# VGA.net
KiCad netlist of a schematic drawn in Altium Designer
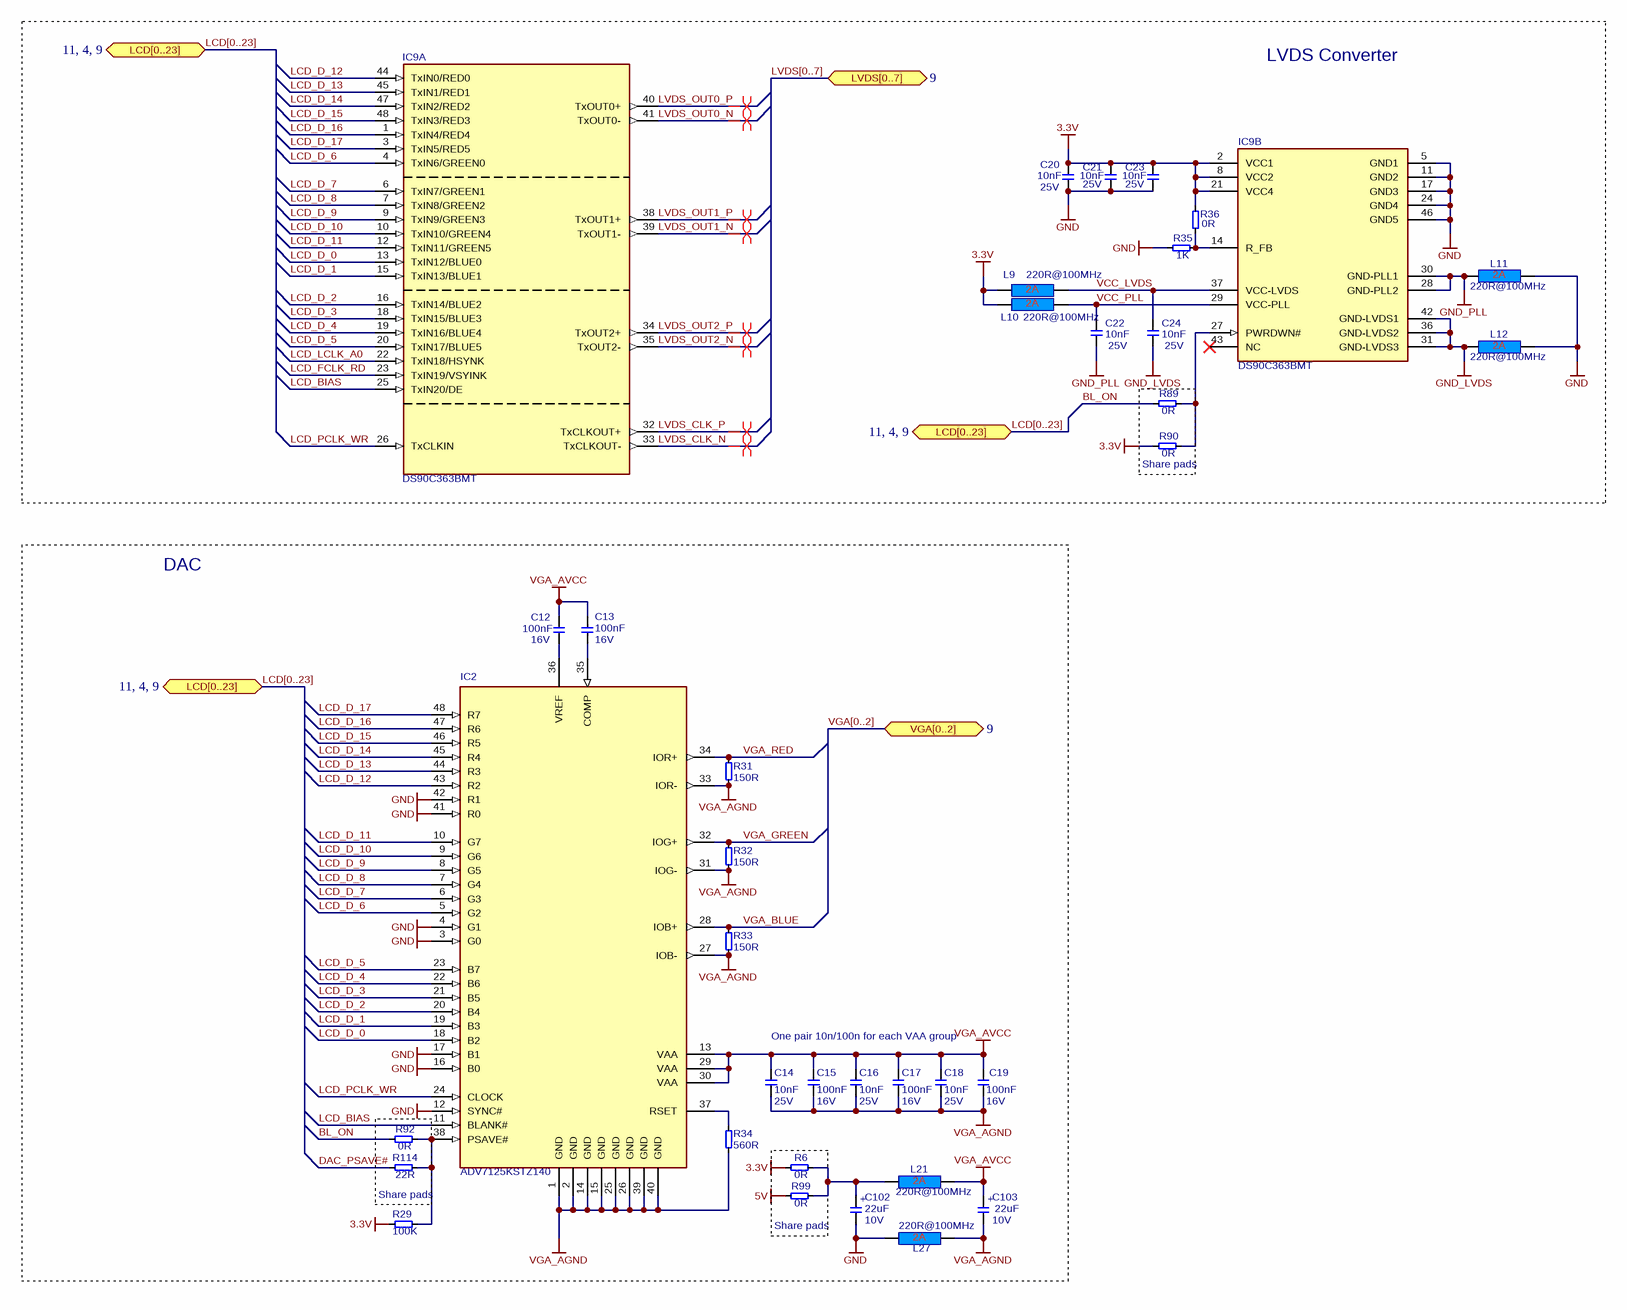
[diagram p0: VGA.SchDoc]

(export (version "E")
  (design (tool "Eeschema 10.0.6"))
  (components
    (comp (ref "C12")
      (value "100nF")
      (footprint "T_CAPC0603X33N")
      (description "Capacitor Ceramic X7R 100nF 16V 10% 0603")
      (fields (field (name "TOLERANCE") "10%") (field (name "RATING") "16V"))
      (libsource (lib "Iris") (part "C-X7R-100nF-16V-10%-0603"))
    )
    (comp (ref "C13")
      (value "100nF")
      (footprint "T_CAPC0603X33N")
      (description "Capacitor Ceramic X7R 100nF 16V 10% 0603")
      (fields (field (name "TOLERANCE") "10%") (field (name "RATING") "16V"))
      (libsource (lib "Iris") (part "C-X7R-100nF-16V-10%-0603"))
    )
    (comp (ref "C14")
      (value "10nF")
      (footprint "T_CAPC0603X33N")
      (description "Capacitor Ceramic X7R 10nF 25V 10% 0603")
      (fields (field (name "TOLERANCE") "10%") (field (name "RATING") "25V"))
      (libsource (lib "Iris") (part "C-X7R-10nF-25V-10%-0603"))
    )
    (comp (ref "C15")
      (value "100nF")
      (footprint "T_CAPC0603X33N")
      (description "Capacitor Ceramic X7R 100nF 16V 10% 0603")
      (fields (field (name "TOLERANCE") "10%") (field (name "RATING") "16V"))
      (libsource (lib "Iris") (part "C-X7R-100nF-16V-10%-0603"))
    )
    (comp (ref "C16")
      (value "10nF")
      (footprint "T_CAPC0603X33N")
      (description "Capacitor Ceramic X7R 10nF 25V 10% 0603")
      (fields (field (name "TOLERANCE") "10%") (field (name "RATING") "25V"))
      (libsource (lib "Iris") (part "C-X7R-10nF-25V-10%-0603"))
    )
    (comp (ref "C17")
      (value "100nF")
      (footprint "T_CAPC0603X33N")
      (description "Capacitor Ceramic X7R 100nF 16V 10% 0603")
      (fields (field (name "TOLERANCE") "10%") (field (name "RATING") "16V"))
      (libsource (lib "Iris") (part "C-X7R-100nF-16V-10%-0603"))
    )
    (comp (ref "C18")
      (value "10nF")
      (footprint "T_CAPC0603X33N")
      (description "Capacitor Ceramic X7R 10nF 25V 10% 0603")
      (fields (field (name "TOLERANCE") "10%") (field (name "RATING") "25V"))
      (libsource (lib "Iris") (part "C-X7R-10nF-25V-10%-0603"))
    )
    (comp (ref "C19")
      (value "100nF")
      (footprint "T_CAPC0603X33N")
      (description "Capacitor Ceramic X7R 100nF 16V 10% 0603")
      (fields (field (name "TOLERANCE") "10%") (field (name "RATING") "16V"))
      (libsource (lib "Iris") (part "C-X7R-100nF-16V-10%-0603"))
    )
    (comp (ref "C20")
      (value "10nF")
      (footprint "T_CAPC0603X33N")
      (description "Capacitor Ceramic X7R 10nF 25V 10% 0603")
      (fields (field (name "TOLERANCE") "10%") (field (name "RATING") "25V"))
      (libsource (lib "Iris") (part "C-X7R-10nF-25V-10%-0603"))
    )
    (comp (ref "C21")
      (value "10nF")
      (footprint "T_CAPC0603X33N")
      (description "Capacitor Ceramic X7R 10nF 25V 10% 0603")
      (fields (field (name "TOLERANCE") "10%") (field (name "RATING") "25V"))
      (libsource (lib "Iris") (part "C-X7R-10nF-25V-10%-0603"))
    )
    (comp (ref "C22")
      (value "10nF")
      (footprint "T_CAPC0603X33N")
      (description "Capacitor Ceramic X7R 10nF 25V 10% 0603")
      (fields (field (name "TOLERANCE") "10%") (field (name "RATING") "25V"))
      (libsource (lib "Iris") (part "C-X7R-10nF-25V-10%-0603"))
    )
    (comp (ref "C23")
      (value "10nF")
      (footprint "T_CAPC0603X33N")
      (description "Capacitor Ceramic X7R 10nF 25V 10% 0603")
      (fields (field (name "TOLERANCE") "10%") (field (name "RATING") "25V"))
      (libsource (lib "Iris") (part "C-X7R-10nF-25V-10%-0603"))
    )
    (comp (ref "C24")
      (value "10nF")
      (footprint "T_CAPC0603X33N")
      (description "Capacitor Ceramic X7R 10nF 25V 10% 0603")
      (fields (field (name "TOLERANCE") "10%") (field (name "RATING") "25V"))
      (libsource (lib "Iris") (part "C-X7R-10nF-25V-10%-0603"))
    )
    (comp (ref "C102")
      (value "22uF")
      (footprint "CAPMP3528X210N")
      (description "Capacitor TA 22uF 10V 20% 3528")
      (fields (field (name "TOLERANCE") "20%") (field (name "RATING") "10V"))
      (libsource (lib "Iris") (part "C-TA-22uF-10V-20%-3528"))
    )
    (comp (ref "C103")
      (value "22uF")
      (footprint "CAPMP3528X210N")
      (description "Capacitor TA 22uF 10V 20% 3528")
      (fields (field (name "TOLERANCE") "20%") (field (name "RATING") "10V"))
      (libsource (lib "Iris") (part "C-TA-22uF-10V-20%-3528"))
    )
    (comp (ref "IC2")
      (value "ADV7125KSTZ140")
      (footprint "QFP50P900X900X120-48N")
      (description "Video DAC 8bit 140MHz")
      (fields (field (name "MANUFACTURER PART NO.") "ADV7125KSTZ140"))
      (libsource (lib "Iris") (part "IC-AD-ADV7125KSTZ140"))
    )
    (comp (ref "IC9")
      (value "DS90C363BMT")
      (footprint "SOP50P810X120-48N")
      (description "LVDS Converter")
      (fields (field (name "MANUFACTURER PART NO.") "DS90C363BMT"))
      (libsource (lib "Iris") (part "IC-NS-DS90C363BMT"))
    )
    (comp (ref "L9")
      (value "220R@100MHz")
      (footprint "INDC1608X95N")
      (description "220R@100MHz 2A EMI FILTER")
      (fields (field (name "TOLERANCE") "25%"))
      (libsource (lib "Iris") (part "L-220R@100MHz-2A-25%-0603"))
    )
    (comp (ref "L10")
      (value "220R@100MHz")
      (footprint "INDC1608X95N")
      (description "220R@100MHz 2A EMI FILTER")
      (fields (field (name "TOLERANCE") "25%"))
      (libsource (lib "Iris") (part "L-220R@100MHz-2A-25%-0603"))
    )
    (comp (ref "L11")
      (value "220R@100MHz")
      (footprint "INDC1608X95N")
      (description "220R@100MHz 2A EMI FILTER")
      (fields (field (name "TOLERANCE") "25%"))
      (libsource (lib "Iris") (part "L-220R@100MHz-2A-25%-0603"))
    )
    (comp (ref "L12")
      (value "220R@100MHz")
      (footprint "INDC1608X95N")
      (description "220R@100MHz 2A EMI FILTER")
      (fields (field (name "TOLERANCE") "25%"))
      (libsource (lib "Iris") (part "L-220R@100MHz-2A-25%-0603"))
    )
    (comp (ref "L21")
      (value "220R@100MHz")
      (footprint "INDC1608X95N")
      (description "220R@100MHz 2A EMI FILTER")
      (fields (field (name "TOLERANCE") "25%"))
      (libsource (lib "Iris") (part "L-220R@100MHz-2A-25%-0603"))
    )
    (comp (ref "L27")
      (value "220R@100MHz")
      (footprint "INDC1608X95N")
      (description "220R@100MHz 2A EMI FILTER")
      (fields (field (name "TOLERANCE") "25%"))
      (libsource (lib "Iris") (part "L-220R@100MHz-2A-25%-0603"))
    )
    (comp (ref "R6")
      (value "0R")
      (footprint "T_RESC0603X30N")
      (description "Resistor 0 ohm 63mW 1% 0603")
      (fields (field (name "TOLERANCE") "1%"))
      (libsource (lib "Iris") (part "R-0R-63mW-1%-0603"))
    )
    (comp (ref "R29")
      (value "100K")
      (footprint "T_RESC0603X30N")
      (description "Resistor 100 Kohm 63mW 5% 0603")
      (fields (field (name "TOLERANCE") "5%"))
      (libsource (lib "Iris") (part "R-100KR-63mW-5%-0603"))
    )
    (comp (ref "R31")
      (value "150R")
      (footprint "T_RESC0603X30N")
      (description "Resistor 150 ohm 63mW 1% 0603")
      (fields (field (name "TOLERANCE") "1%"))
      (libsource (lib "Iris") (part "R-150R-63mW-1%-0603"))
    )
    (comp (ref "R32")
      (value "150R")
      (footprint "T_RESC0603X30N")
      (description "Resistor 150 ohm 63mW 1% 0603")
      (fields (field (name "TOLERANCE") "1%"))
      (libsource (lib "Iris") (part "R-150R-63mW-1%-0603"))
    )
    (comp (ref "R33")
      (value "150R")
      (footprint "T_RESC0603X30N")
      (description "Resistor 150 ohm 63mW 1% 0603")
      (fields (field (name "TOLERANCE") "1%"))
      (libsource (lib "Iris") (part "R-150R-63mW-1%-0603"))
    )
    (comp (ref "R34")
      (value "560R")
      (footprint "t_RESC0603X30N")
      (description "Resistor 560 ohm 63mW 5% 0603")
      (fields (field (name "TOLERANCE") "5%"))
      (libsource (lib "Iris") (part "R-560R-63mW-5%-0603"))
    )
    (comp (ref "R35")
      (value "1K")
      (footprint "t_RESC0603X30N")
      (description "Resistor 1 Kohm 63mW 5% 0603")
      (fields (field (name "TOLERANCE") "5%"))
      (libsource (lib "Iris") (part "R-1KR-63mW-5%-0603"))
    )
    (comp (ref "R36")
      (value "0R")
      (footprint "t_RESC0603X30N")
      (description "Resistor 0 ohm 63mW 1% 0603")
      (fields (field (name "TOLERANCE") "1%"))
      (libsource (lib "Iris") (part "R-0R-63mW-1%-0603"))
    )
    (comp (ref "R89")
      (value "0R")
      (footprint "t_RESC0603X30N")
      (description "Resistor 0 ohm 63mW 1% 0603")
      (fields (field (name "TOLERANCE") "1%"))
      (libsource (lib "Iris") (part "R-0R-63mW-1%-0603"))
    )
    (comp (ref "R90")
      (value "0R")
      (footprint "t_RESC0603X30N")
      (description "Resistor 0 ohm 63mW 1% 0603")
      (fields (field (name "TOLERANCE") "1%"))
      (libsource (lib "Iris") (part "R-0R-63mW-1%-0603"))
    )
    (comp (ref "R92")
      (value "0R")
      (footprint "T_RESC0603X30N")
      (description "Resistor 0 ohm 63mW 1% 0603")
      (fields (field (name "TOLERANCE") "1%"))
      (libsource (lib "Iris") (part "R-0R-63mW-1%-0603"))
    )
    (comp (ref "R99")
      (value "0R")
      (footprint "T_RESC0603X30N")
      (description "Resistor 0 ohm 63mW 1% 0603")
      (fields (field (name "TOLERANCE") "1%"))
      (libsource (lib "Iris") (part "R-0R-63mW-1%-0603"))
    )
    (comp (ref "R114")
      (value "22R")
      (footprint "T_RESC0603X30N")
      (description "Resistor 22 ohm 63mW 5% 0603")
      (fields (field (name "TOLERANCE") "5%"))
      (libsource (lib "Iris") (part "R-22R-63mW-5%-0603"))
    )
  )
  (nets
    (net (code "36") (name "/BL_ON") (class "Default")
      (node (ref "R89") (pin "1") (pinfunction "1_1") (pintype "passive"))
      (node (ref "R92") (pin "1") (pinfunction "1_1") (pintype "passive"))
    )
    (net (code "37") (name "/DAC_PSAVE#") (class "Default")
      (node (ref "R114") (pin "1") (pinfunction "1_1") (pintype "passive"))
    )
    (net (code "39") (name "/LCD_BIAS") (class "Default")
      (node (ref "IC2") (pin "11") (pinfunction "BLANK#_11") (pintype "input"))
      (node (ref "IC9") (pin "25") (pinfunction "TxIN20/DE_25") (pintype "input"))
    )
    (net (code "40") (name "/LCD_D_0") (class "Default")
      (node (ref "IC2") (pin "18") (pinfunction "B2_18") (pintype "input"))
      (node (ref "IC9") (pin "13") (pinfunction "TxIN12/BLUE0_13") (pintype "input"))
    )
    (net (code "41") (name "/LCD_D_1") (class "Default")
      (node (ref "IC2") (pin "19") (pinfunction "B3_19") (pintype "input"))
      (node (ref "IC9") (pin "15") (pinfunction "TxIN13/BLUE1_15") (pintype "input"))
    )
    (net (code "42") (name "/LCD_D_2") (class "Default")
      (node (ref "IC2") (pin "20") (pinfunction "B4_20") (pintype "input"))
      (node (ref "IC9") (pin "16") (pinfunction "TxIN14/BLUE2_16") (pintype "input"))
    )
    (net (code "43") (name "/LCD_D_3") (class "Default")
      (node (ref "IC2") (pin "21") (pinfunction "B5_21") (pintype "input"))
      (node (ref "IC9") (pin "18") (pinfunction "TxIN15/BLUE3_18") (pintype "input"))
    )
    (net (code "44") (name "/LCD_D_4") (class "Default")
      (node (ref "IC2") (pin "22") (pinfunction "B6_22") (pintype "input"))
      (node (ref "IC9") (pin "19") (pinfunction "TxIN16/BLUE4_19") (pintype "input"))
    )
    (net (code "45") (name "/LCD_D_5") (class "Default")
      (node (ref "IC2") (pin "23") (pinfunction "B7_23") (pintype "input"))
      (node (ref "IC9") (pin "20") (pinfunction "TxIN17/BLUE5_20") (pintype "input"))
    )
    (net (code "46") (name "/LCD_D_6") (class "Default")
      (node (ref "IC2") (pin "5") (pinfunction "G2_5") (pintype "input"))
      (node (ref "IC9") (pin "4") (pinfunction "TxIN6/GREEN0_4") (pintype "input"))
    )
    (net (code "47") (name "/LCD_D_7") (class "Default")
      (node (ref "IC2") (pin "6") (pinfunction "G3_6") (pintype "input"))
      (node (ref "IC9") (pin "6") (pinfunction "TxIN7/GREEN1_6") (pintype "input"))
    )
    (net (code "48") (name "/LCD_D_8") (class "Default")
      (node (ref "IC2") (pin "7") (pinfunction "G4_7") (pintype "input"))
      (node (ref "IC9") (pin "7") (pinfunction "TxIN8/GREEN2_7") (pintype "input"))
    )
    (net (code "49") (name "/LCD_D_9") (class "Default")
      (node (ref "IC2") (pin "8") (pinfunction "G5_8") (pintype "input"))
      (node (ref "IC9") (pin "9") (pinfunction "TxIN9/GREEN3_9") (pintype "input"))
    )
    (net (code "50") (name "/LCD_D_10") (class "Default")
      (node (ref "IC2") (pin "9") (pinfunction "G6_9") (pintype "input"))
      (node (ref "IC9") (pin "10") (pinfunction "TxIN10/GREEN4_10") (pintype "input"))
    )
    (net (code "51") (name "/LCD_D_11") (class "Default")
      (node (ref "IC2") (pin "10") (pinfunction "G7_10") (pintype "input"))
      (node (ref "IC9") (pin "12") (pinfunction "TxIN11/GREEN5_12") (pintype "input"))
    )
    (net (code "52") (name "/LCD_D_12") (class "Default")
      (node (ref "IC2") (pin "43") (pinfunction "R2_43") (pintype "input"))
      (node (ref "IC9") (pin "44") (pinfunction "TxIN0/RED0_44") (pintype "input"))
    )
    (net (code "53") (name "/LCD_D_13") (class "Default")
      (node (ref "IC2") (pin "44") (pinfunction "R3_44") (pintype "input"))
      (node (ref "IC9") (pin "45") (pinfunction "TxIN1/RED1_45") (pintype "input"))
    )
    (net (code "54") (name "/LCD_D_14") (class "Default")
      (node (ref "IC2") (pin "45") (pinfunction "R4_45") (pintype "input"))
      (node (ref "IC9") (pin "47") (pinfunction "TxIN2/RED2_47") (pintype "input"))
    )
    (net (code "55") (name "/LCD_D_15") (class "Default")
      (node (ref "IC2") (pin "46") (pinfunction "R5_46") (pintype "input"))
      (node (ref "IC9") (pin "48") (pinfunction "TxIN3/RED3_48") (pintype "input"))
    )
    (net (code "56") (name "/LCD_D_16") (class "Default")
      (node (ref "IC2") (pin "47") (pinfunction "R6_47") (pintype "input"))
      (node (ref "IC9") (pin "1") (pinfunction "TxIN4/RED4_1") (pintype "input"))
    )
    (net (code "57") (name "/LCD_D_17") (class "Default")
      (node (ref "IC2") (pin "48") (pinfunction "R7_48") (pintype "input"))
      (node (ref "IC9") (pin "3") (pinfunction "TxIN5/RED5_3") (pintype "input"))
    )
    (net (code "58") (name "/LCD_FCLK_RD") (class "Default")
      (node (ref "IC9") (pin "23") (pinfunction "TxIN19/VSYINK_23") (pintype "input"))
    )
    (net (code "59") (name "/LCD_LCLK_A0") (class "Default")
      (node (ref "IC9") (pin "22") (pinfunction "TxIN18/HSYNK_22") (pintype "input"))
    )
    (net (code "60") (name "/LCD_PCLK_WR") (class "Default")
      (node (ref "IC2") (pin "24") (pinfunction "CLOCK_24") (pintype "input"))
      (node (ref "IC9") (pin "26") (pinfunction "TxCLKIN_26") (pintype "input"))
    )
    (net (code "62") (name "/LVDS_CLK_N") (class "Default")
      (node (ref "IC9") (pin "33") (pinfunction "TxCLKOUT-_33") (pintype "output"))
    )
    (net (code "63") (name "/LVDS_CLK_P") (class "Default")
      (node (ref "IC9") (pin "32") (pinfunction "TxCLKOUT+_32") (pintype "output"))
    )
    (net (code "64") (name "/LVDS_OUT0_N") (class "Default")
      (node (ref "IC9") (pin "41") (pinfunction "TxOUT0-_41") (pintype "output"))
    )
    (net (code "65") (name "/LVDS_OUT0_P") (class "Default")
      (node (ref "IC9") (pin "40") (pinfunction "TxOUT0+_40") (pintype "output"))
    )
    (net (code "66") (name "/LVDS_OUT1_N") (class "Default")
      (node (ref "IC9") (pin "39") (pinfunction "TxOUT1-_39") (pintype "output"))
    )
    (net (code "67") (name "/LVDS_OUT1_P") (class "Default")
      (node (ref "IC9") (pin "38") (pinfunction "TxOUT1+_38") (pintype "output"))
    )
    (net (code "68") (name "/LVDS_OUT2_N") (class "Default")
      (node (ref "IC9") (pin "35") (pinfunction "TxOUT2-_35") (pintype "output"))
    )
    (net (code "69") (name "/LVDS_OUT2_P") (class "Default")
      (node (ref "IC9") (pin "34") (pinfunction "TxOUT2+_34") (pintype "output"))
    )
    (net (code "70") (name "/VCC_LVDS") (class "Default")
      (node (ref "C24") (pin "2") (pinfunction "2_2") (pintype "passive"))
      (node (ref "IC9") (pin "37") (pinfunction "VCC-LVDS_37") (pintype "power_in"))
      (node (ref "L9") (pin "2") (pinfunction "2_2") (pintype "passive"))
    )
    (net (code "71") (name "/VCC_PLL") (class "Default")
      (node (ref "C22") (pin "2") (pinfunction "2_2") (pintype "passive"))
      (node (ref "IC9") (pin "29") (pinfunction "VCC-PLL_29") (pintype "power_in"))
      (node (ref "L10") (pin "2") (pinfunction "2_2") (pintype "passive"))
    )
    (net (code "73") (name "/VGA_BLUE") (class "Default")
      (node (ref "IC2") (pin "28") (pinfunction "IOB+_28") (pintype "output"))
      (node (ref "R33") (pin "2") (pinfunction "2_2") (pintype "passive"))
    )
    (net (code "74") (name "/VGA_GREEN") (class "Default")
      (node (ref "IC2") (pin "32") (pinfunction "IOG+_32") (pintype "output"))
      (node (ref "R32") (pin "2") (pinfunction "2_2") (pintype "passive"))
    )
    (net (code "75") (name "/VGA_RED") (class "Default")
      (node (ref "IC2") (pin "34") (pinfunction "IOR+_34") (pintype "output"))
      (node (ref "R31") (pin "2") (pinfunction "2_2") (pintype "passive"))
    )
    (net (code "76") (name "3.3V") (class "Default")
      (node (ref "C20") (pin "2") (pinfunction "2_2") (pintype "passive"))
      (node (ref "C21") (pin "2") (pinfunction "2_2") (pintype "passive"))
      (node (ref "C23") (pin "2") (pinfunction "2_2") (pintype "passive"))
      (node (ref "IC9") (pin "2") (pinfunction "VCC1_2") (pintype "power_in"))
      (node (ref "IC9") (pin "21") (pinfunction "VCC4_21") (pintype "power_in"))
      (node (ref "IC9") (pin "8") (pinfunction "VCC2_8") (pintype "power_in"))
      (node (ref "L10") (pin "1") (pinfunction "1_1") (pintype "passive"))
      (node (ref "L9") (pin "1") (pinfunction "1_1") (pintype "passive"))
      (node (ref "R29") (pin "1") (pinfunction "1_1") (pintype "passive"))
      (node (ref "R36") (pin "2") (pinfunction "2_2") (pintype "passive"))
      (node (ref "R6") (pin "1") (pinfunction "1_1") (pintype "passive"))
      (node (ref "R90") (pin "1") (pinfunction "1_1") (pintype "passive"))
    )
    (net (code "77") (name "5V") (class "Default")
      (node (ref "R99") (pin "1") (pinfunction "1_1") (pintype "passive"))
    )
    (net (code "78") (name "GND") (class "Default")
      (node (ref "C102") (pin "2") (pinfunction "2_2") (pintype "passive"))
      (node (ref "C20") (pin "1") (pinfunction "1_1") (pintype "passive"))
      (node (ref "C21") (pin "1") (pinfunction "1_1") (pintype "passive"))
      (node (ref "C23") (pin "1") (pinfunction "1_1") (pintype "passive"))
      (node (ref "IC2") (pin "12") (pinfunction "SYNC#_12") (pintype "input"))
      (node (ref "IC2") (pin "16") (pinfunction "B0_16") (pintype "input"))
      (node (ref "IC2") (pin "17") (pinfunction "B1_17") (pintype "input"))
      (node (ref "IC2") (pin "3") (pinfunction "G0_3") (pintype "input"))
      (node (ref "IC2") (pin "4") (pinfunction "G1_4") (pintype "input"))
      (node (ref "IC2") (pin "41") (pinfunction "R0_41") (pintype "input"))
      (node (ref "IC2") (pin "42") (pinfunction "R1_42") (pintype "input"))
      (node (ref "IC9") (pin "11") (pinfunction "GND2_11") (pintype "power_in"))
      (node (ref "IC9") (pin "17") (pinfunction "GND3_17") (pintype "power_in"))
      (node (ref "IC9") (pin "24") (pinfunction "GND4_24") (pintype "power_in"))
      (node (ref "IC9") (pin "46") (pinfunction "GND5_46") (pintype "power_in"))
      (node (ref "IC9") (pin "5") (pinfunction "GND1_5") (pintype "power_in"))
      (node (ref "L11") (pin "2") (pinfunction "2_2") (pintype "passive"))
      (node (ref "L12") (pin "2") (pinfunction "2_2") (pintype "passive"))
      (node (ref "L27") (pin "1") (pinfunction "1_1") (pintype "passive"))
      (node (ref "R35") (pin "1") (pinfunction "1_1") (pintype "passive"))
    )
    (net (code "79") (name "GND_LVDS") (class "Default")
      (node (ref "C24") (pin "1") (pinfunction "1_1") (pintype "passive"))
      (node (ref "IC9") (pin "31") (pinfunction "GND-LVDS3_31") (pintype "power_in"))
      (node (ref "IC9") (pin "36") (pinfunction "GND-LVDS2_36") (pintype "power_in"))
      (node (ref "IC9") (pin "42") (pinfunction "GND-LVDS1_42") (pintype "power_in"))
      (node (ref "L12") (pin "1") (pinfunction "1_1") (pintype "passive"))
    )
    (net (code "80") (name "GND_PLL") (class "Default")
      (node (ref "C22") (pin "1") (pinfunction "1_1") (pintype "passive"))
      (node (ref "IC9") (pin "28") (pinfunction "GND-PLL2_28") (pintype "power_in"))
      (node (ref "IC9") (pin "30") (pinfunction "GND-PLL1_30") (pintype "power_in"))
      (node (ref "L11") (pin "1") (pinfunction "1_1") (pintype "passive"))
    )
    (net (code "81") (name "Net-(C102-Pad1)") (class "Default")
      (node (ref "C102") (pin "1") (pinfunction "1_1") (pintype "passive"))
      (node (ref "L21") (pin "1") (pinfunction "1_1") (pintype "passive"))
      (node (ref "R6") (pin "2") (pinfunction "2_2") (pintype "passive"))
      (node (ref "R99") (pin "2") (pinfunction "2_2") (pintype "passive"))
    )
    (net (code "82") (name "Net-(IC2-COMP)") (class "Default")
      (node (ref "C13") (pin "1") (pinfunction "1_1") (pintype "passive"))
      (node (ref "IC2") (pin "35") (pinfunction "COMP_35") (pintype "input"))
    )
    (net (code "83") (name "Net-(IC2-PSAVE#)") (class "Default")
      (node (ref "IC2") (pin "38") (pinfunction "PSAVE#_38") (pintype "input"))
      (node (ref "R114") (pin "2") (pinfunction "2_2") (pintype "passive"))
      (node (ref "R29") (pin "2") (pinfunction "2_2") (pintype "passive"))
      (node (ref "R92") (pin "2") (pinfunction "2_2") (pintype "passive"))
    )
    (net (code "84") (name "Net-(IC2-RSET)") (class "Default")
      (node (ref "IC2") (pin "37") (pinfunction "RSET_37") (pintype "passive"))
      (node (ref "R34") (pin "2") (pinfunction "2_2") (pintype "passive"))
    )
    (net (code "85") (name "Net-(IC2-VREF)") (class "Default")
      (node (ref "C12") (pin "1") (pinfunction "1_1") (pintype "passive"))
      (node (ref "IC2") (pin "36") (pinfunction "VREF_36") (pintype "power_in"))
    )
    (net (code "86") (name "Net-(IC9B-PWRDWN#)") (class "Default")
      (node (ref "IC9") (pin "27") (pinfunction "PWRDWN#_27") (pintype "input"))
      (node (ref "R89") (pin "2") (pinfunction "2_2") (pintype "passive"))
      (node (ref "R90") (pin "2") (pinfunction "2_2") (pintype "passive"))
    )
    (net (code "87") (name "Net-(IC9B-R_FB)") (class "Default")
      (node (ref "IC9") (pin "14") (pinfunction "R_FB_14") (pintype "power_in"))
      (node (ref "R35") (pin "2") (pinfunction "2_2") (pintype "passive"))
      (node (ref "R36") (pin "1") (pinfunction "1_1") (pintype "passive"))
    )
    (net (code "88") (name "VGA_AGND") (class "Default")
      (node (ref "C103") (pin "2") (pinfunction "2_2") (pintype "passive"))
      (node (ref "C14") (pin "1") (pinfunction "1_1") (pintype "passive"))
      (node (ref "C15") (pin "1") (pinfunction "1_1") (pintype "passive"))
      (node (ref "C16") (pin "1") (pinfunction "1_1") (pintype "passive"))
      (node (ref "C17") (pin "1") (pinfunction "1_1") (pintype "passive"))
      (node (ref "C18") (pin "1") (pinfunction "1_1") (pintype "passive"))
      (node (ref "C19") (pin "1") (pinfunction "1_1") (pintype "passive"))
      (node (ref "IC2") (pin "1") (pinfunction "GND_1") (pintype "power_in"))
      (node (ref "IC2") (pin "14") (pinfunction "GND_14") (pintype "power_in"))
      (node (ref "IC2") (pin "15") (pinfunction "GND_15") (pintype "power_in"))
      (node (ref "IC2") (pin "2") (pinfunction "GND_2") (pintype "power_in"))
      (node (ref "IC2") (pin "25") (pinfunction "GND_25") (pintype "power_in"))
      (node (ref "IC2") (pin "26") (pinfunction "GND_26") (pintype "power_in"))
      (node (ref "IC2") (pin "27") (pinfunction "IOB-_27") (pintype "output"))
      (node (ref "IC2") (pin "31") (pinfunction "IOG-_31") (pintype "output"))
      (node (ref "IC2") (pin "33") (pinfunction "IOR-_33") (pintype "output"))
      (node (ref "IC2") (pin "39") (pinfunction "GND_39") (pintype "power_in"))
      (node (ref "IC2") (pin "40") (pinfunction "GND_40") (pintype "power_in"))
      (node (ref "L27") (pin "2") (pinfunction "2_2") (pintype "passive"))
      (node (ref "R31") (pin "1") (pinfunction "1_1") (pintype "passive"))
      (node (ref "R32") (pin "1") (pinfunction "1_1") (pintype "passive"))
      (node (ref "R33") (pin "1") (pinfunction "1_1") (pintype "passive"))
      (node (ref "R34") (pin "1") (pinfunction "1_1") (pintype "passive"))
    )
    (net (code "89") (name "VGA_AVCC") (class "Default")
      (node (ref "C103") (pin "1") (pinfunction "1_1") (pintype "passive"))
      (node (ref "C12") (pin "2") (pinfunction "2_2") (pintype "passive"))
      (node (ref "C13") (pin "2") (pinfunction "2_2") (pintype "passive"))
      (node (ref "C14") (pin "2") (pinfunction "2_2") (pintype "passive"))
      (node (ref "C15") (pin "2") (pinfunction "2_2") (pintype "passive"))
      (node (ref "C16") (pin "2") (pinfunction "2_2") (pintype "passive"))
      (node (ref "C17") (pin "2") (pinfunction "2_2") (pintype "passive"))
      (node (ref "C18") (pin "2") (pinfunction "2_2") (pintype "passive"))
      (node (ref "C19") (pin "2") (pinfunction "2_2") (pintype "passive"))
      (node (ref "IC2") (pin "13") (pinfunction "VAA_13") (pintype "power_in"))
      (node (ref "IC2") (pin "29") (pinfunction "VAA_29") (pintype "power_in"))
      (node (ref "IC2") (pin "30") (pinfunction "VAA_30") (pintype "power_in"))
      (node (ref "L21") (pin "2") (pinfunction "2_2") (pintype "passive"))
    )
    (net (code "90") (name "unconnected-(IC9B-NC-Pad43)") (class "Default")
      (node (ref "IC9") (pin "43") (pinfunction "NC_43") (pintype "passive+no_connect"))
    )
  )
)
